# gondola_old.net
KiCad netlist of a schematic drawn in EAGLE
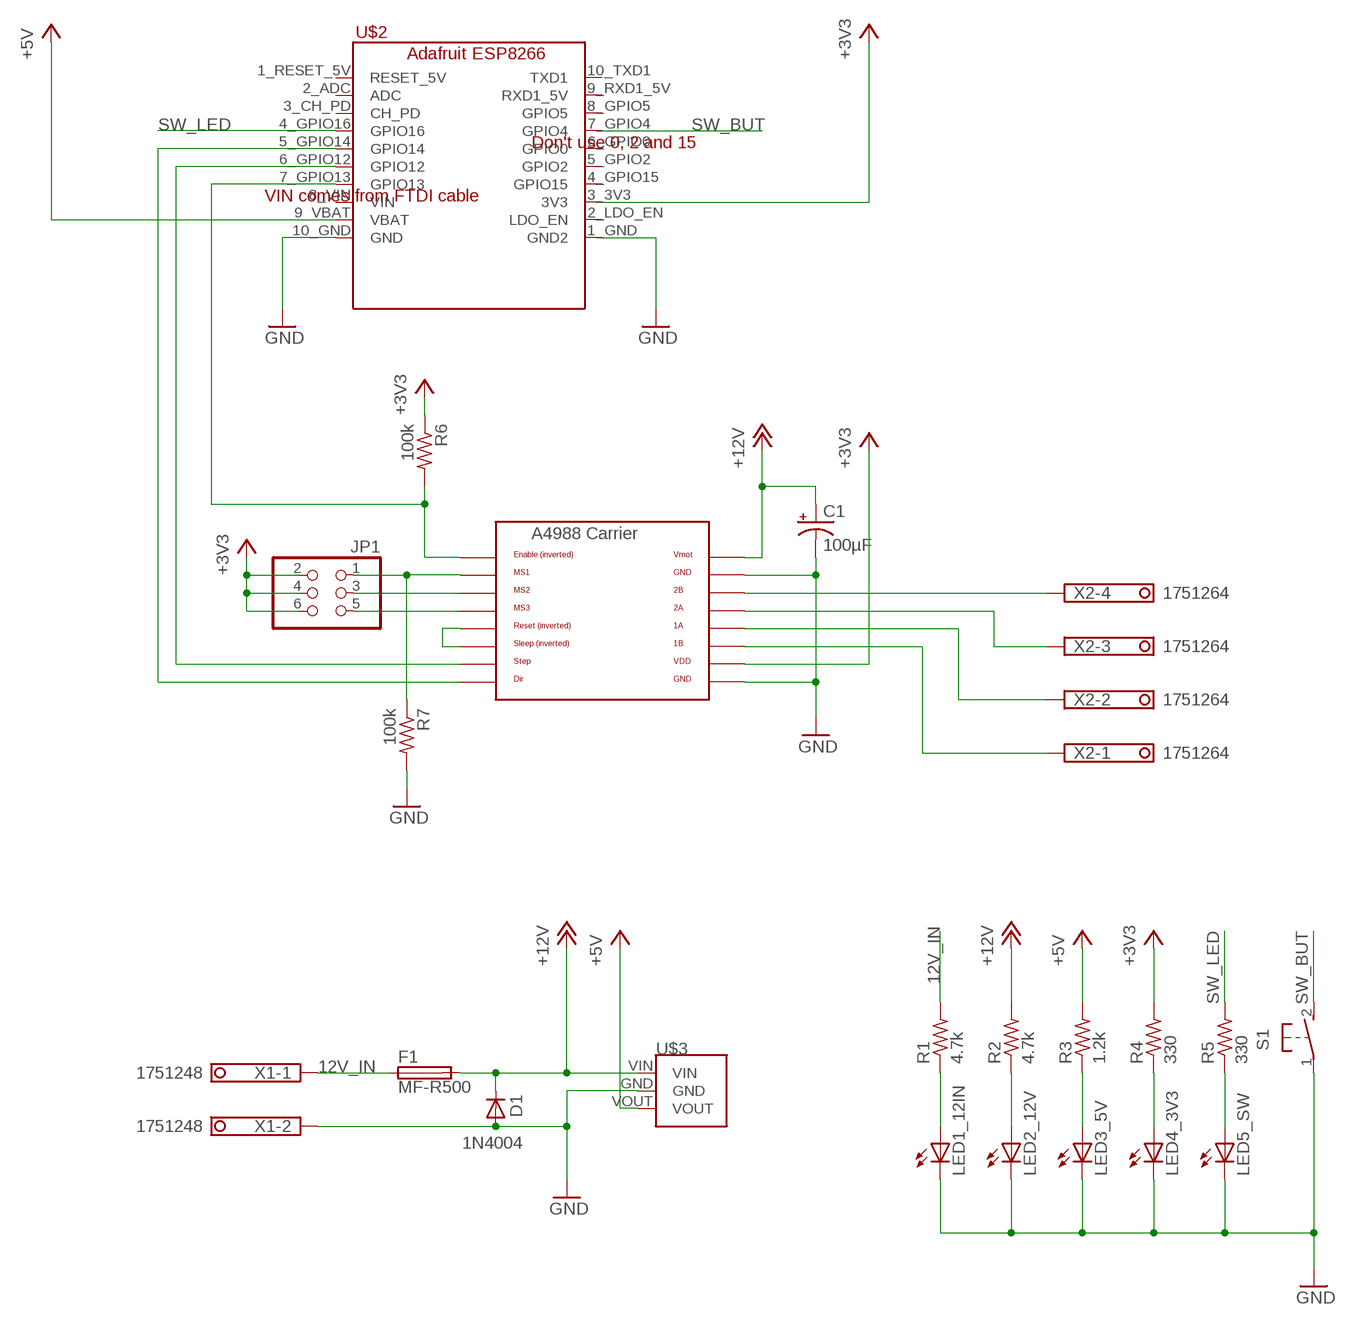
[diagram p0: schematic, sheet 1]

(export (version "E")
  (design (tool "Eeschema 10.0.6"))
  (components
    (comp (ref "C1")
      (value "100µF")
      (footprint "eagle-import:153CLV-0605")
      (libsource (lib "eagle-import") (part "CPOL-US153CLV-0605"))
    )
    (comp (ref "D1")
      (value "1N4004")
      (footprint "eagle-import:DO41-10")
      (libsource (lib "eagle-import") (part "1N4004"))
    )
    (comp (ref "F1")
      (value "MF-R500")
      (footprint "eagle-import:LITTLEFUSE")
      (libsource (lib "eagle-import") (part "PTCFUSE"))
    )
    (comp (ref "JP1")
      (value "PINHD-2X3")
      (footprint "eagle-import:2X03")
      (libsource (lib "eagle-import") (part "PINHD-2X3"))
    )
    (comp (ref "LED1_12IN")
      (value "LEDCHIP-LED0805")
      (footprint "eagle-import:CHIP-LED0805")
      (libsource (lib "eagle-import") (part "LEDCHIP-LED0805"))
    )
    (comp (ref "LED2_12V")
      (value "LEDCHIP-LED0805")
      (footprint "eagle-import:CHIP-LED0805")
      (libsource (lib "eagle-import") (part "LEDCHIP-LED0805"))
    )
    (comp (ref "LED3_5V")
      (value "LEDCHIP-LED0805")
      (footprint "eagle-import:CHIP-LED0805")
      (libsource (lib "eagle-import") (part "LEDCHIP-LED0805"))
    )
    (comp (ref "LED4_3V3")
      (value "LEDCHIP-LED0805")
      (footprint "eagle-import:CHIP-LED0805")
      (libsource (lib "eagle-import") (part "LEDCHIP-LED0805"))
    )
    (comp (ref "LED5_SW")
      (value "LEDCHIP-LED0805")
      (footprint "eagle-import:CHIP-LED0805")
      (libsource (lib "eagle-import") (part "LEDCHIP-LED0805"))
    )
    (comp (ref "R1")
      (value "4.7k")
      (footprint "eagle-import:R0805")
      (libsource (lib "eagle-import") (part "R-US_R0805"))
    )
    (comp (ref "R2")
      (value "4.7k")
      (footprint "eagle-import:R0805")
      (libsource (lib "eagle-import") (part "R-US_R0805"))
    )
    (comp (ref "R3")
      (value "1.2k")
      (footprint "eagle-import:R0805")
      (libsource (lib "eagle-import") (part "R-US_R0805"))
    )
    (comp (ref "R4")
      (value "330")
      (footprint "eagle-import:R0805")
      (libsource (lib "eagle-import") (part "R-US_R0805"))
    )
    (comp (ref "R5")
      (value "330")
      (footprint "eagle-import:R0805")
      (libsource (lib "eagle-import") (part "R-US_R0805"))
    )
    (comp (ref "R6")
      (value "100k")
      (footprint "eagle-import:R0805")
      (libsource (lib "eagle-import") (part "R-US_R0805"))
    )
    (comp (ref "R7")
      (value "100k")
      (footprint "eagle-import:R0805")
      (libsource (lib "eagle-import") (part "R-US_R0805"))
    )
    (comp (ref "S1")
      (value "31-XX")
      (footprint "eagle-import:B3F-31XX")
      (fields (field (name "MPN") "B3F-3100"))
      (libsource (lib "eagle-import") (part "31-XX"))
    )
    (comp (ref "U$1")
      (value "A4988BREAKOUT")
      (footprint "eagle-import:A4988BREAKOUT")
      (libsource (lib "eagle-import") (part "A4988BREAKOUT"))
    )
    (comp (ref "U$2")
      (value "ADAFRUIT_ESP8266")
      (footprint "eagle-import:ADAFRUIT_ESP8266")
      (libsource (lib "eagle-import") (part "ADAFRUIT_ESP8266"))
    )
    (comp (ref "U$3")
      (value "ROHM_BP5293-XX")
      (footprint "eagle-import:ROHM_BP5293-XX")
      (libsource (lib "eagle-import") (part "ROHM_BP5293-XX"))
    )
    (comp (ref "X1")
      (value "1751248")
      (footprint "eagle-import:1751248")
      (libsource (lib "eagle-import") (part "1751248"))
    )
    (comp (ref "X2")
      (value "1751264")
      (footprint "eagle-import:1751264")
      (libsource (lib "eagle-import") (part "1751264"))
    )
  )
  (nets
    (net (code "1") (name "+3V3") (class "Default")
      (node (ref "JP1") (pin "2") (pinfunction "2_2") (pintype "passive"))
      (node (ref "JP1") (pin "4") (pinfunction "4_4") (pintype "passive"))
      (node (ref "JP1") (pin "6") (pinfunction "6_6") (pintype "passive"))
      (node (ref "R4") (pin "2") (pinfunction "2_2") (pintype "passive"))
      (node (ref "R6") (pin "1") (pinfunction "1_1") (pintype "passive"))
      (node (ref "U$1") (pin "VDD") (pinfunction "VDD_VDD") (pintype "power_in"))
      (node (ref "U$2") (pin "3_3V3") (pinfunction "3V3_3_3V3") (pintype "bidirectional"))
    )
    (net (code "2") (name "+5V") (class "Default")
      (node (ref "R3") (pin "2") (pinfunction "2_2") (pintype "passive"))
      (node (ref "U$2") (pin "9_VBAT") (pinfunction "VBAT_9_VBAT") (pintype "bidirectional"))
      (node (ref "U$3") (pin "VOUT") (pinfunction "VOUT_VOUT") (pintype "bidirectional"))
    )
    (net (code "3") (name "+12V") (class "Default")
      (node (ref "C1") (pin "+") (pinfunction "+_+") (pintype "passive"))
      (node (ref "D1") (pin "C") (pinfunction "C_C") (pintype "passive"))
      (node (ref "F1") (pin "2") (pinfunction "2_2") (pintype "passive"))
      (node (ref "R2") (pin "2") (pinfunction "2_2") (pintype "passive"))
      (node (ref "U$1") (pin "VMOT") (pinfunction "VMOT_VMOT") (pintype "power_in"))
      (node (ref "U$3") (pin "VIN") (pinfunction "VIN_VIN") (pintype "bidirectional"))
    )
    (net (code "4") (name "/12V_IN") (class "Default")
      (node (ref "F1") (pin "1") (pinfunction "1_1") (pintype "passive"))
      (node (ref "R1") (pin "2") (pinfunction "2_2") (pintype "passive"))
      (node (ref "X1") (pin "1") (pinfunction "K_1") (pintype "passive"))
    )
    (net (code "5") (name "/SW_BUT") (class "Default")
      (node (ref "S1") (pin "2") (pinfunction "S_2") (pintype "passive"))
      (node (ref "U$2") (pin "7_GPIO4") (pinfunction "GPIO4_7_GPIO4") (pintype "bidirectional"))
    )
    (net (code "6") (name "/SW_LED") (class "Default")
      (node (ref "R5") (pin "2") (pinfunction "2_2") (pintype "passive"))
      (node (ref "U$2") (pin "4_GPIO16") (pinfunction "GPIO16_4_GPIO16") (pintype "bidirectional"))
    )
    (net (code "7") (name "GND") (class "Default")
      (node (ref "C1") (pin "-") (pinfunction "-_-") (pintype "passive"))
      (node (ref "D1") (pin "A") (pinfunction "A_A") (pintype "passive"))
      (node (ref "LED1_12IN") (pin "C") (pinfunction "C_C") (pintype "passive"))
      (node (ref "LED2_12V") (pin "C") (pinfunction "C_C") (pintype "passive"))
      (node (ref "LED3_5V") (pin "C") (pinfunction "C_C") (pintype "passive"))
      (node (ref "LED4_3V3") (pin "C") (pinfunction "C_C") (pintype "passive"))
      (node (ref "LED5_SW") (pin "C") (pinfunction "C_C") (pintype "passive"))
      (node (ref "R7") (pin "2") (pinfunction "2_2") (pintype "passive"))
      (node (ref "S1") (pin "1") (pinfunction "P_1") (pintype "passive"))
      (node (ref "U$1") (pin "GND") (pinfunction "GND_GND") (pintype "power_in"))
      (node (ref "U$1") (pin "GND@0") (pinfunction "GND_GND@0") (pintype "power_in"))
      (node (ref "U$2") (pin "10_GND") (pinfunction "GND_10_GND") (pintype "bidirectional"))
      (node (ref "U$2") (pin "1_GND") (pinfunction "GND2_1_GND") (pintype "bidirectional"))
      (node (ref "U$3") (pin "GND") (pinfunction "GND_GND") (pintype "bidirectional"))
      (node (ref "X1") (pin "2") (pinfunction "K_2") (pintype "passive"))
    )
    (net (code "8") (name "Net-(JP1-Pad1)") (class "Default")
      (node (ref "JP1") (pin "1") (pinfunction "1_1") (pintype "passive"))
      (node (ref "R7") (pin "1") (pinfunction "1_1") (pintype "passive"))
      (node (ref "U$1") (pin "MS1") (pinfunction "MS1_MS1") (pintype "input"))
    )
    (net (code "9") (name "Net-(JP1-Pad3)") (class "Default")
      (node (ref "JP1") (pin "3") (pinfunction "3_3") (pintype "passive"))
      (node (ref "U$1") (pin "MS2") (pinfunction "MS2_MS2") (pintype "input"))
    )
    (net (code "10") (name "Net-(JP1-Pad5)") (class "Default")
      (node (ref "JP1") (pin "5") (pinfunction "5_5") (pintype "passive"))
      (node (ref "U$1") (pin "MS3") (pinfunction "MS3_MS3") (pintype "input"))
    )
    (net (code "11") (name "Net-(LED1_12IN-PadA)") (class "Default")
      (node (ref "LED1_12IN") (pin "A") (pinfunction "A_A") (pintype "passive"))
      (node (ref "R1") (pin "1") (pinfunction "1_1") (pintype "passive"))
    )
    (net (code "12") (name "Net-(LED2_12V-PadA)") (class "Default")
      (node (ref "LED2_12V") (pin "A") (pinfunction "A_A") (pintype "passive"))
      (node (ref "R2") (pin "1") (pinfunction "1_1") (pintype "passive"))
    )
    (net (code "13") (name "Net-(LED3_5V-PadA)") (class "Default")
      (node (ref "LED3_5V") (pin "A") (pinfunction "A_A") (pintype "passive"))
      (node (ref "R3") (pin "1") (pinfunction "1_1") (pintype "passive"))
    )
    (net (code "14") (name "Net-(LED4_3V3-PadA)") (class "Default")
      (node (ref "LED4_3V3") (pin "A") (pinfunction "A_A") (pintype "passive"))
      (node (ref "R4") (pin "1") (pinfunction "1_1") (pintype "passive"))
    )
    (net (code "15") (name "Net-(LED5_SW-PadA)") (class "Default")
      (node (ref "LED5_SW") (pin "A") (pinfunction "A_A") (pintype "passive"))
      (node (ref "R5") (pin "1") (pinfunction "1_1") (pintype "passive"))
    )
    (net (code "16") (name "Net-(U$1-SLEEP)") (class "Default")
      (node (ref "U$1") (pin "RST") (pinfunction "RST_RST") (pintype "input"))
      (node (ref "U$1") (pin "SLP") (pinfunction "SLEEP_SLP") (pintype "input"))
    )
    (net (code "17") (name "Net-(U$2-GPIO12)") (class "Default")
      (node (ref "U$1") (pin "STEP") (pinfunction "STEP_STEP") (pintype "input"))
      (node (ref "U$2") (pin "6_GPIO12") (pinfunction "GPIO12_6_GPIO12") (pintype "bidirectional"))
    )
    (net (code "18") (name "Net-(U$2-GPIO13)") (class "Default")
      (node (ref "R6") (pin "2") (pinfunction "2_2") (pintype "passive"))
      (node (ref "U$1") (pin "EN") (pinfunction "EN_EN") (pintype "input"))
      (node (ref "U$2") (pin "7_GPIO13") (pinfunction "GPIO13_7_GPIO13") (pintype "bidirectional"))
    )
    (net (code "19") (name "Net-(U$2-GPIO14)") (class "Default")
      (node (ref "U$1") (pin "DIR") (pinfunction "DIR_DIR") (pintype "input"))
      (node (ref "U$2") (pin "5_GPIO14") (pinfunction "GPIO14_5_GPIO14") (pintype "bidirectional"))
    )
    (net (code "20") (name "Net-(X2A-K)") (class "Default")
      (node (ref "U$1") (pin "1B") (pinfunction "1B_1B") (pintype "output"))
      (node (ref "X2") (pin "1") (pinfunction "K_1") (pintype "passive"))
    )
    (net (code "21") (name "Net-(X2B-K)") (class "Default")
      (node (ref "U$1") (pin "1A") (pinfunction "1A_1A") (pintype "output"))
      (node (ref "X2") (pin "2") (pinfunction "K_2") (pintype "passive"))
    )
    (net (code "22") (name "Net-(X2C-K)") (class "Default")
      (node (ref "U$1") (pin "2A") (pinfunction "2A_2A") (pintype "output"))
      (node (ref "X2") (pin "3") (pinfunction "K_3") (pintype "passive"))
    )
    (net (code "23") (name "Net-(X2D-K)") (class "Default")
      (node (ref "U$1") (pin "2B") (pinfunction "2B_2B") (pintype "output"))
      (node (ref "X2") (pin "4") (pinfunction "K_4") (pintype "passive"))
    )
    (net (code "24") (name "unconnected-(U$2-ADC-Pad2_ADC)") (class "Default")
      (node (ref "U$2") (pin "2_ADC") (pinfunction "ADC_2_ADC") (pintype "bidirectional"))
    )
    (net (code "25") (name "unconnected-(U$2-CH_PD-Pad3_CH_PD)") (class "Default")
      (node (ref "U$2") (pin "3_CH_PD") (pinfunction "CH_PD_3_CH_PD") (pintype "bidirectional"))
    )
    (net (code "26") (name "unconnected-(U$2-GPIO0-Pad6_GPIO0)") (class "Default")
      (node (ref "U$2") (pin "6_GPIO0") (pinfunction "GPIO0_6_GPIO0") (pintype "bidirectional"))
    )
    (net (code "27") (name "unconnected-(U$2-GPIO2-Pad5_GPIO2)") (class "Default")
      (node (ref "U$2") (pin "5_GPIO2") (pinfunction "GPIO2_5_GPIO2") (pintype "bidirectional"))
    )
    (net (code "28") (name "unconnected-(U$2-GPIO5-Pad8_GPIO5)") (class "Default")
      (node (ref "U$2") (pin "8_GPIO5") (pinfunction "GPIO5_8_GPIO5") (pintype "bidirectional"))
    )
    (net (code "29") (name "unconnected-(U$2-GPIO15-Pad4_GPIO15)") (class "Default")
      (node (ref "U$2") (pin "4_GPIO15") (pinfunction "GPIO15_4_GPIO15") (pintype "bidirectional"))
    )
    (net (code "30") (name "unconnected-(U$2-LDO_EN-Pad2_LDO_EN)") (class "Default")
      (node (ref "U$2") (pin "2_LDO_EN") (pinfunction "LDO_EN_2_LDO_EN") (pintype "bidirectional"))
    )
    (net (code "31") (name "unconnected-(U$2-RESET_5V-Pad1_RESET_5V)") (class "Default")
      (node (ref "U$2") (pin "1_RESET_5V") (pinfunction "RESET_5V_1_RESET_5V") (pintype "bidirectional"))
    )
    (net (code "32") (name "unconnected-(U$2-RXD1_5V-Pad9_RXD1_5V)") (class "Default")
      (node (ref "U$2") (pin "9_RXD1_5V") (pinfunction "RXD1_5V_9_RXD1_5V") (pintype "bidirectional"))
    )
    (net (code "33") (name "unconnected-(U$2-TXD1-Pad10_TXD1)") (class "Default")
      (node (ref "U$2") (pin "10_TXD1") (pinfunction "TXD1_10_TXD1") (pintype "bidirectional"))
    )
    (net (code "34") (name "unconnected-(U$2-VIN-Pad8_VIN)") (class "Default")
      (node (ref "U$2") (pin "8_VIN") (pinfunction "VIN_8_VIN") (pintype "bidirectional"))
    )
  )
)
